# 1.net
KiCad netlist of a schematic drawn in Altium Designer
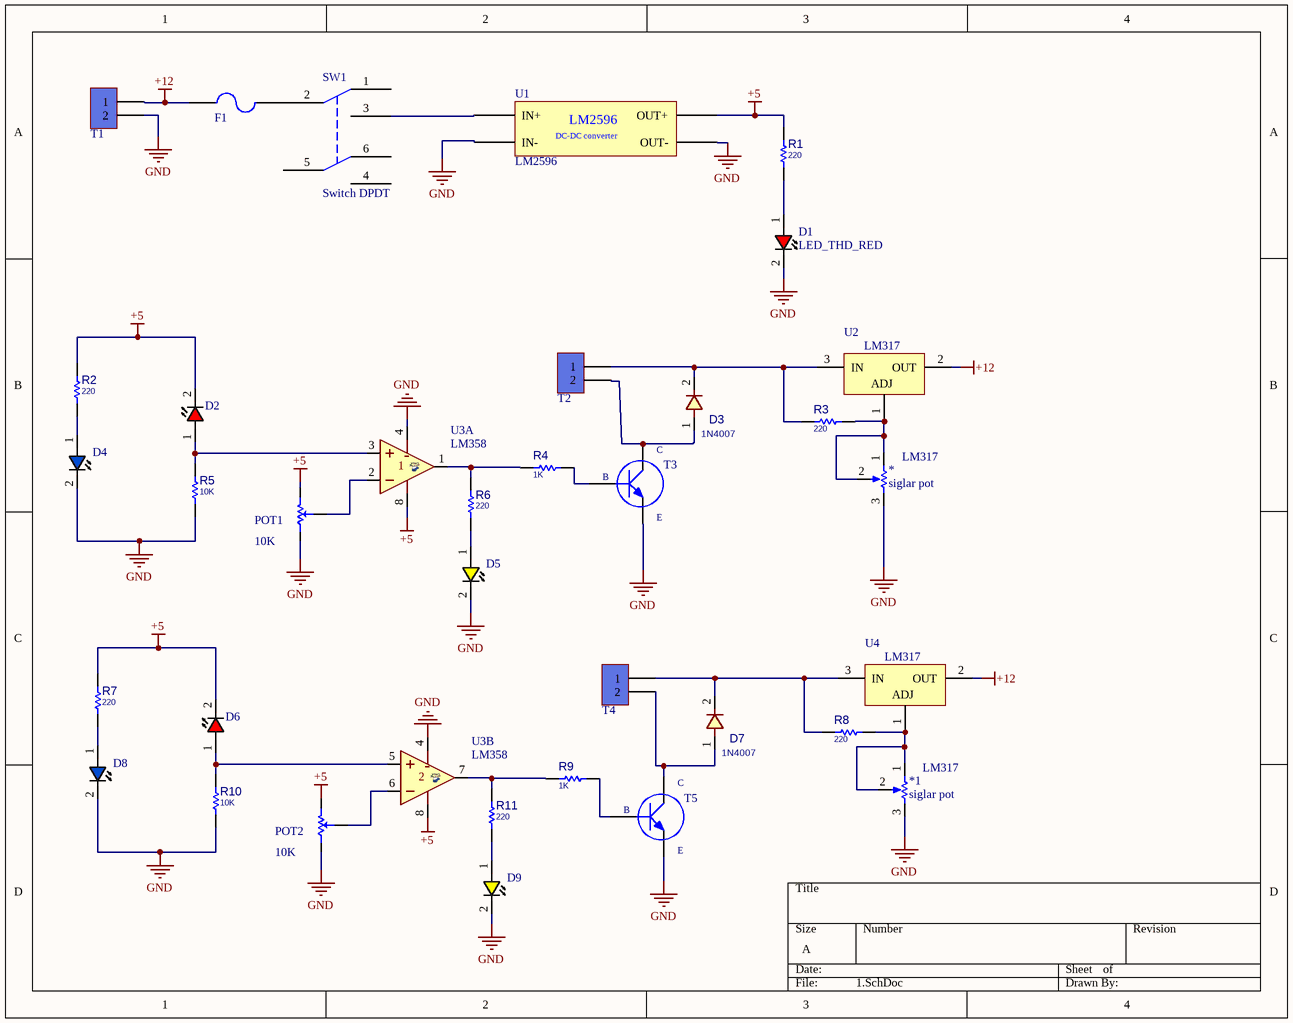
[diagram p0: 1.SchDoc]

(export (version "E")
  (design (tool "Eeschema 10.0.6"))
  (components
    (comp (ref "*") (value "siglar pot") (footprint "VOL_R") (libsource (lib "POT") (part "siglar pot")))
    (comp (ref "*1") (value "siglar pot") (footprint "VOL_R") (libsource (lib "POT") (part "siglar pot")))
    (comp (ref "D1")
      (value "LED_THD_RED")
      (footprint "LED5MM_RED")
      (description "LED, THD, RED")
      (libsource (lib "Diode_LED") (part "LED_THD_RED"))
    )
    (comp (ref "D2")
      (value "LED_THD_RED")
      (footprint "LED5MM_RED")
      (description "LED, THD, RED")
      (libsource (lib "Diode_LED") (part "LED_THD_RED"))
    )
    (comp (ref "D3")
      (value "1N4007")
      (footprint "D_AX04_DO41")
      (description "DIODE, GENERAL PURPOSE, 1000V/1A")
      (fields (field (name "MANF") "Diodes"))
      (libsource (lib "Diode") (part "DIODE_THD_1N4007"))
    )
    (comp (ref "D4")
      (value "LED_THD_BLU")
      (footprint "LED5MM_BLU")
      (description "LED, THD, BLU")
      (libsource (lib "Diode_LED") (part "LED_THD_BLU"))
    )
    (comp (ref "D5")
      (value "LED_THD_YLW")
      (footprint "LED5MM_YLO")
      (description "LED, THD, YELLOW")
      (libsource (lib "Diode_LED") (part "LED_THD_YLW"))
    )
    (comp (ref "D6")
      (value "LED_THD_RED")
      (footprint "LED5MM_RED")
      (description "LED, THD, RED")
      (libsource (lib "Diode_LED") (part "LED_THD_RED"))
    )
    (comp (ref "D7")
      (value "1N4007")
      (footprint "D_AX04_DO41")
      (description "DIODE, GENERAL PURPOSE, 1000V/1A")
      (fields (field (name "MANF") "Diodes"))
      (libsource (lib "Diode") (part "DIODE_THD_1N4007"))
    )
    (comp (ref "D8")
      (value "LED_THD_BLU")
      (footprint "LED5MM_BLU")
      (description "LED, THD, BLU")
      (libsource (lib "Diode_LED") (part "LED_THD_BLU"))
    )
    (comp (ref "D9")
      (value "LED_THD_YLW")
      (footprint "LED5MM_YLO")
      (description "LED, THD, YELLOW")
      (libsource (lib "Diode_LED") (part "LED_THD_YLW"))
    )
    (comp (ref "F1")
      (value "F=1.0 A")
      (footprint "Fuse 5x20 With holder pin")
      (description "Fuses 5x20")
      (fields (field (name "DESIGNER") "Abbas Basereh"))
      (libsource (lib "Altium") (part "Fuse 5x20 with holdeer pins"))
    )
    (comp (ref "POT1")
      (value "10K")
      (footprint "POT 4")
      (description "Variable Resistor")
      (libsource (lib "Altium") (part "POT"))
    )
    (comp (ref "POT2")
      (value "10K")
      (footprint "POT 4")
      (description "Variable Resistor")
      (libsource (lib "Altium") (part "POT"))
    )
    (comp (ref "R1")
      (value "220")
      (footprint "R025W_AX04")
      (description "RESISTOR, THD")
      (fields (field (name "MANF_P#") "RK73H1ETTP4701F") (field (name "MANF") "KOA SPEER"))
      (libsource (lib "PASSIVE") (part "RES_THD"))
    )
    (comp (ref "R2")
      (value "220")
      (footprint "R025W_AX04")
      (description "RESISTOR, THD")
      (fields (field (name "MANF_P#") "RK73H1ETTP4701F") (field (name "MANF") "KOA SPEER"))
      (libsource (lib "PASSIVE") (part "RES_THD"))
    )
    (comp (ref "R3")
      (value "220")
      (footprint "R025W_AX04")
      (description "RESISTOR, THD")
      (fields (field (name "MANF_P#") "RK73H1ETTP4701F") (field (name "MANF") "KOA SPEER"))
      (libsource (lib "PASSIVE") (part "RES_THD"))
    )
    (comp (ref "R4")
      (value "1K")
      (footprint "R025W_AX04")
      (description "RESISTOR, THD")
      (fields (field (name "MANF_P#") "RK73H1ETTP4701F") (field (name "MANF") "KOA SPEER"))
      (libsource (lib "PASSIVE") (part "RES_THD"))
    )
    (comp (ref "R5")
      (value "10K")
      (footprint "R025W_AX04")
      (description "RESISTOR, THD")
      (fields (field (name "MANF_P#") "RK73H1ETTP4701F") (field (name "MANF") "KOA SPEER"))
      (libsource (lib "PASSIVE") (part "RES_THD"))
    )
    (comp (ref "R6")
      (value "220")
      (footprint "R025W_AX04")
      (description "RESISTOR, THD")
      (fields (field (name "MANF_P#") "RK73H1ETTP4701F") (field (name "MANF") "KOA SPEER"))
      (libsource (lib "PASSIVE") (part "RES_THD"))
    )
    (comp (ref "R7")
      (value "220")
      (footprint "R025W_AX04")
      (description "RESISTOR, THD")
      (fields (field (name "MANF_P#") "RK73H1ETTP4701F") (field (name "MANF") "KOA SPEER"))
      (libsource (lib "PASSIVE") (part "RES_THD"))
    )
    (comp (ref "R8")
      (value "220")
      (footprint "R025W_AX04")
      (description "RESISTOR, THD")
      (fields (field (name "MANF_P#") "RK73H1ETTP4701F") (field (name "MANF") "KOA SPEER"))
      (libsource (lib "PASSIVE") (part "RES_THD"))
    )
    (comp (ref "R9")
      (value "1K")
      (footprint "R025W_AX04")
      (description "RESISTOR, THD")
      (fields (field (name "MANF_P#") "RK73H1ETTP4701F") (field (name "MANF") "KOA SPEER"))
      (libsource (lib "PASSIVE") (part "RES_THD"))
    )
    (comp (ref "R10")
      (value "10K")
      (footprint "R025W_AX04")
      (description "RESISTOR, THD")
      (fields (field (name "MANF_P#") "RK73H1ETTP4701F") (field (name "MANF") "KOA SPEER"))
      (libsource (lib "PASSIVE") (part "RES_THD"))
    )
    (comp (ref "R11")
      (value "220")
      (footprint "R025W_AX04")
      (description "RESISTOR, THD")
      (fields (field (name "MANF_P#") "RK73H1ETTP4701F") (field (name "MANF") "KOA SPEER"))
      (libsource (lib "PASSIVE") (part "RES_THD"))
    )
    (comp (ref "SW1")
      (value "Switch DPDT")
      (footprint "Switch DPDT")
      (libsource (lib "pushbutton6pin") (part "Switch DPDT"))
    )
    (comp (ref "T1")
      (value "KF301_Terminal")
      (footprint "KF301 2PIN")
      (description "Terminal 2 Pin 250VAC 16A")
      (fields (field (name "DESIGNER") "Abbas Basereh"))
      (libsource (lib "Altium") (part "KF301-2Pin_Terminal"))
    )
    (comp (ref "T2")
      (value "KF301_Terminal")
      (footprint "KF301 2PIN")
      (description "Terminal 2 Pin 250VAC 16A")
      (fields (field (name "DESIGNER") "Abbas Basereh"))
      (libsource (lib "Altium") (part "KF301-2Pin_Terminal"))
    )
    (comp (ref "T3") (value "NPN") (footprint "TO-220") (libsource (lib "transistor") (part "TIP41")))
    (comp (ref "T4")
      (value "KF301_Terminal")
      (footprint "KF301 2PIN")
      (description "Terminal 2 Pin 250VAC 16A")
      (fields (field (name "DESIGNER") "Abbas Basereh"))
      (libsource (lib "Altium") (part "KF301-2Pin_Terminal"))
    )
    (comp (ref "T5") (value "NPN") (footprint "TO-220") (libsource (lib "transistor") (part "TIP41")))
    (comp (ref "U1")
      (value "LM2596")
      (footprint "LM2596_MODULE")
      (description "DC-DC converter")
      (libsource (lib "Module") (part "LM2596_ADJ"))
    )
    (comp (ref "U2") (value "LM317") (footprint "TO-220") (libsource (lib "Regulators") (part "LM317")))
    (comp (ref "U3")
      (value "LM358")
      (footprint "DIP_8")
      (description "AMP, Dual, Low-Power")
      (fields (field (name "MANF") "Texas Instruments, Fairchild") (field (name "MANF_P#") "LM358AN"))
      (libsource (lib "Amp") (part "LM358_DIP8"))
    )
    (comp (ref "U4") (value "LM317") (footprint "TO-220") (libsource (lib "Regulators") (part "LM317")))
  )
  (nets
    (net (code "1") (name "+5") (class "Default")
      (node (ref "D2") (pin "2") (pinfunction "CATHODE_2") (pintype "passive"))
      (node (ref "D6") (pin "2") (pinfunction "CATHODE_2") (pintype "passive"))
      (node (ref "POT1") (pin "2") (pinfunction "CW_2") (pintype "passive"))
      (node (ref "POT2") (pin "2") (pinfunction "CW_2") (pintype "passive"))
      (node (ref "R1") (pin "2") (pinfunction "2_2") (pintype "passive"))
      (node (ref "R2") (pin "2") (pinfunction "2_2") (pintype "passive"))
      (node (ref "R7") (pin "2") (pinfunction "2_2") (pintype "passive"))
      (node (ref "U1") (pin "4") (pinfunction "OUT+_4") (pintype "passive"))
      (node (ref "U3") (pin "8") (pinfunction "V+_8") (pintype "passive"))
    )
    (net (code "2") (name "+12") (class "Default")
      (node (ref "F1") (pin "1") (pinfunction "1_1") (pintype "passive"))
      (node (ref "T1") (pin "1") (pinfunction "1_1") (pintype "passive"))
      (node (ref "U2") (pin "2") (pinfunction "OUT_2") (pintype "power_in"))
      (node (ref "U4") (pin "2") (pinfunction "OUT_2") (pintype "power_in"))
    )
    (net (code "3") (name "GND") (class "Default")
      (node (ref "*") (pin "3") (pinfunction "BOT_3") (pintype "passive"))
      (node (ref "*1") (pin "3") (pinfunction "BOT_3") (pintype "passive"))
      (node (ref "D1") (pin "2") (pinfunction "CATHODE_2") (pintype "passive"))
      (node (ref "D4") (pin "2") (pinfunction "CATHODE_2") (pintype "passive"))
      (node (ref "D5") (pin "2") (pinfunction "CATHODE_2") (pintype "passive"))
      (node (ref "D8") (pin "2") (pinfunction "CATHODE_2") (pintype "passive"))
      (node (ref "D9") (pin "2") (pinfunction "CATHODE_2") (pintype "passive"))
      (node (ref "POT1") (pin "1") (pinfunction "CCW_1") (pintype "passive"))
      (node (ref "POT2") (pin "1") (pinfunction "CCW_1") (pintype "passive"))
      (node (ref "R10") (pin "1") (pinfunction "1_1") (pintype "passive"))
      (node (ref "R5") (pin "1") (pinfunction "1_1") (pintype "passive"))
      (node (ref "T1") (pin "2") (pinfunction "2_2") (pintype "passive"))
      (node (ref "T3") (pin "3") (pinfunction "E_3") (pintype "passive"))
      (node (ref "T5") (pin "3") (pinfunction "E_3") (pintype "passive"))
      (node (ref "U1") (pin "2") (pinfunction "IN-_2") (pintype "passive"))
      (node (ref "U1") (pin "3") (pinfunction "OUT-_3") (pintype "passive"))
      (node (ref "U3") (pin "4") (pinfunction "V-_4") (pintype "passive"))
    )
    (net (code "4") (name "Net-(*-TAP)") (class "Default")
      (node (ref "*") (pin "1") (pinfunction "TOP_1") (pintype "passive"))
      (node (ref "*") (pin "2") (pinfunction "TAP_2") (pintype "passive"))
      (node (ref "R3") (pin "1") (pinfunction "1_1") (pintype "passive"))
      (node (ref "U2") (pin "1") (pinfunction "ADJ_1") (pintype "power_in"))
    )
    (net (code "5") (name "Net-(*1-TAP)") (class "Default")
      (node (ref "*1") (pin "1") (pinfunction "TOP_1") (pintype "passive"))
      (node (ref "*1") (pin "2") (pinfunction "TAP_2") (pintype "passive"))
      (node (ref "R8") (pin "1") (pinfunction "1_1") (pintype "passive"))
      (node (ref "U4") (pin "1") (pinfunction "ADJ_1") (pintype "power_in"))
    )
    (net (code "6") (name "Net-(D1-ANODE)") (class "Default")
      (node (ref "D1") (pin "1") (pinfunction "ANODE_1") (pintype "passive"))
      (node (ref "R1") (pin "1") (pinfunction "1_1") (pintype "passive"))
    )
    (net (code "7") (name "Net-(D2-ANODE)") (class "Default")
      (node (ref "D2") (pin "1") (pinfunction "ANODE_1") (pintype "passive"))
      (node (ref "R5") (pin "2") (pinfunction "2_2") (pintype "passive"))
      (node (ref "U3") (pin "3") (pinfunction "IN+_3") (pintype "passive"))
    )
    (net (code "8") (name "Net-(D4-ANODE)") (class "Default")
      (node (ref "D4") (pin "1") (pinfunction "ANODE_1") (pintype "passive"))
      (node (ref "R2") (pin "1") (pinfunction "1_1") (pintype "passive"))
    )
    (net (code "9") (name "Net-(D5-ANODE)") (class "Default")
      (node (ref "D5") (pin "1") (pinfunction "ANODE_1") (pintype "passive"))
      (node (ref "R6") (pin "1") (pinfunction "1_1") (pintype "passive"))
    )
    (net (code "10") (name "Net-(D6-ANODE)") (class "Default")
      (node (ref "D6") (pin "1") (pinfunction "ANODE_1") (pintype "passive"))
      (node (ref "R10") (pin "2") (pinfunction "2_2") (pintype "passive"))
      (node (ref "U3") (pin "5") (pinfunction "IN+_5") (pintype "passive"))
    )
    (net (code "11") (name "Net-(D8-ANODE)") (class "Default")
      (node (ref "D8") (pin "1") (pinfunction "ANODE_1") (pintype "passive"))
      (node (ref "R7") (pin "1") (pinfunction "1_1") (pintype "passive"))
    )
    (net (code "12") (name "Net-(D9-ANODE)") (class "Default")
      (node (ref "D9") (pin "1") (pinfunction "ANODE_1") (pintype "passive"))
      (node (ref "R11") (pin "1") (pinfunction "1_1") (pintype "passive"))
    )
    (net (code "13") (name "Net-(F1-Pad2)") (class "Default")
      (node (ref "F1") (pin "2") (pinfunction "2_2") (pintype "passive"))
      (node (ref "SW1") (pin "2") (pinfunction "2_2") (pintype "passive"))
    )
    (net (code "14") (name "Net-(POT1-SetPoint)") (class "Default")
      (node (ref "POT1") (pin "3") (pinfunction "SetPoint_3") (pintype "passive"))
      (node (ref "U3") (pin "2") (pinfunction "IN-_2") (pintype "passive"))
    )
    (net (code "15") (name "Net-(POT2-SetPoint)") (class "Default")
      (node (ref "POT2") (pin "3") (pinfunction "SetPoint_3") (pintype "passive"))
      (node (ref "U3") (pin "6") (pinfunction "IN-_6") (pintype "passive"))
    )
    (net (code "16") (name "Net-(T3-B)") (class "Default")
      (node (ref "R4") (pin "1") (pinfunction "1_1") (pintype "passive"))
      (node (ref "T3") (pin "1") (pinfunction "B_1") (pintype "passive"))
    )
    (net (code "17") (name "Net-(T3-C)") (class "Default")
      (node (ref "D3") (pin "1") (pinfunction "1_1") (pintype "passive"))
      (node (ref "T2") (pin "2") (pinfunction "2_2") (pintype "passive"))
      (node (ref "T3") (pin "2") (pinfunction "C_2") (pintype "passive"))
    )
    (net (code "18") (name "Net-(T5-B)") (class "Default")
      (node (ref "R9") (pin "1") (pinfunction "1_1") (pintype "passive"))
      (node (ref "T5") (pin "1") (pinfunction "B_1") (pintype "passive"))
    )
    (net (code "19") (name "Net-(T5-C)") (class "Default")
      (node (ref "D7") (pin "1") (pinfunction "1_1") (pintype "passive"))
      (node (ref "T4") (pin "2") (pinfunction "2_2") (pintype "passive"))
      (node (ref "T5") (pin "2") (pinfunction "C_2") (pintype "passive"))
    )
    (net (code "20") (name "Net-(U1-IN+)") (class "Default")
      (node (ref "SW1") (pin "3") (pinfunction "3_3") (pintype "passive"))
      (node (ref "U1") (pin "1") (pinfunction "IN+_1") (pintype "passive"))
    )
    (net (code "21") (name "Net-(U2-IN)") (class "Default")
      (node (ref "D3") (pin "2") (pinfunction "2_2") (pintype "passive"))
      (node (ref "R3") (pin "2") (pinfunction "2_2") (pintype "passive"))
      (node (ref "T2") (pin "1") (pinfunction "1_1") (pintype "passive"))
      (node (ref "U2") (pin "3") (pinfunction "IN_3") (pintype "power_in"))
    )
    (net (code "22") (name "Net-(U3A-OUT)") (class "Default")
      (node (ref "R4") (pin "2") (pinfunction "2_2") (pintype "passive"))
      (node (ref "R6") (pin "2") (pinfunction "2_2") (pintype "passive"))
      (node (ref "U3") (pin "1") (pinfunction "OUT_1") (pintype "passive"))
    )
    (net (code "23") (name "Net-(U3B-OUT)") (class "Default")
      (node (ref "R11") (pin "2") (pinfunction "2_2") (pintype "passive"))
      (node (ref "R9") (pin "2") (pinfunction "2_2") (pintype "passive"))
      (node (ref "U3") (pin "7") (pinfunction "OUT_7") (pintype "passive"))
    )
    (net (code "24") (name "Net-(U4-IN)") (class "Default")
      (node (ref "D7") (pin "2") (pinfunction "2_2") (pintype "passive"))
      (node (ref "R8") (pin "2") (pinfunction "2_2") (pintype "passive"))
      (node (ref "T4") (pin "1") (pinfunction "1_1") (pintype "passive"))
      (node (ref "U4") (pin "3") (pinfunction "IN_3") (pintype "power_in"))
    )
    (net (code "25") (name "unconnected-(SW1-Pad1)") (class "Default")
      (node (ref "SW1") (pin "1") (pinfunction "1_1") (pintype "passive"))
    )
    (net (code "26") (name "unconnected-(SW1-Pad4)") (class "Default")
      (node (ref "SW1") (pin "4") (pinfunction "4_4") (pintype "passive"))
    )
    (net (code "27") (name "unconnected-(SW1-Pad5)") (class "Default")
      (node (ref "SW1") (pin "5") (pinfunction "5_5") (pintype "passive"))
    )
    (net (code "28") (name "unconnected-(SW1-Pad6)") (class "Default")
      (node (ref "SW1") (pin "6") (pinfunction "6_6") (pintype "passive"))
    )
  )
)
